# SwitchRouter1x6c.net
KiCad netlist of a schematic drawn in EAGLE
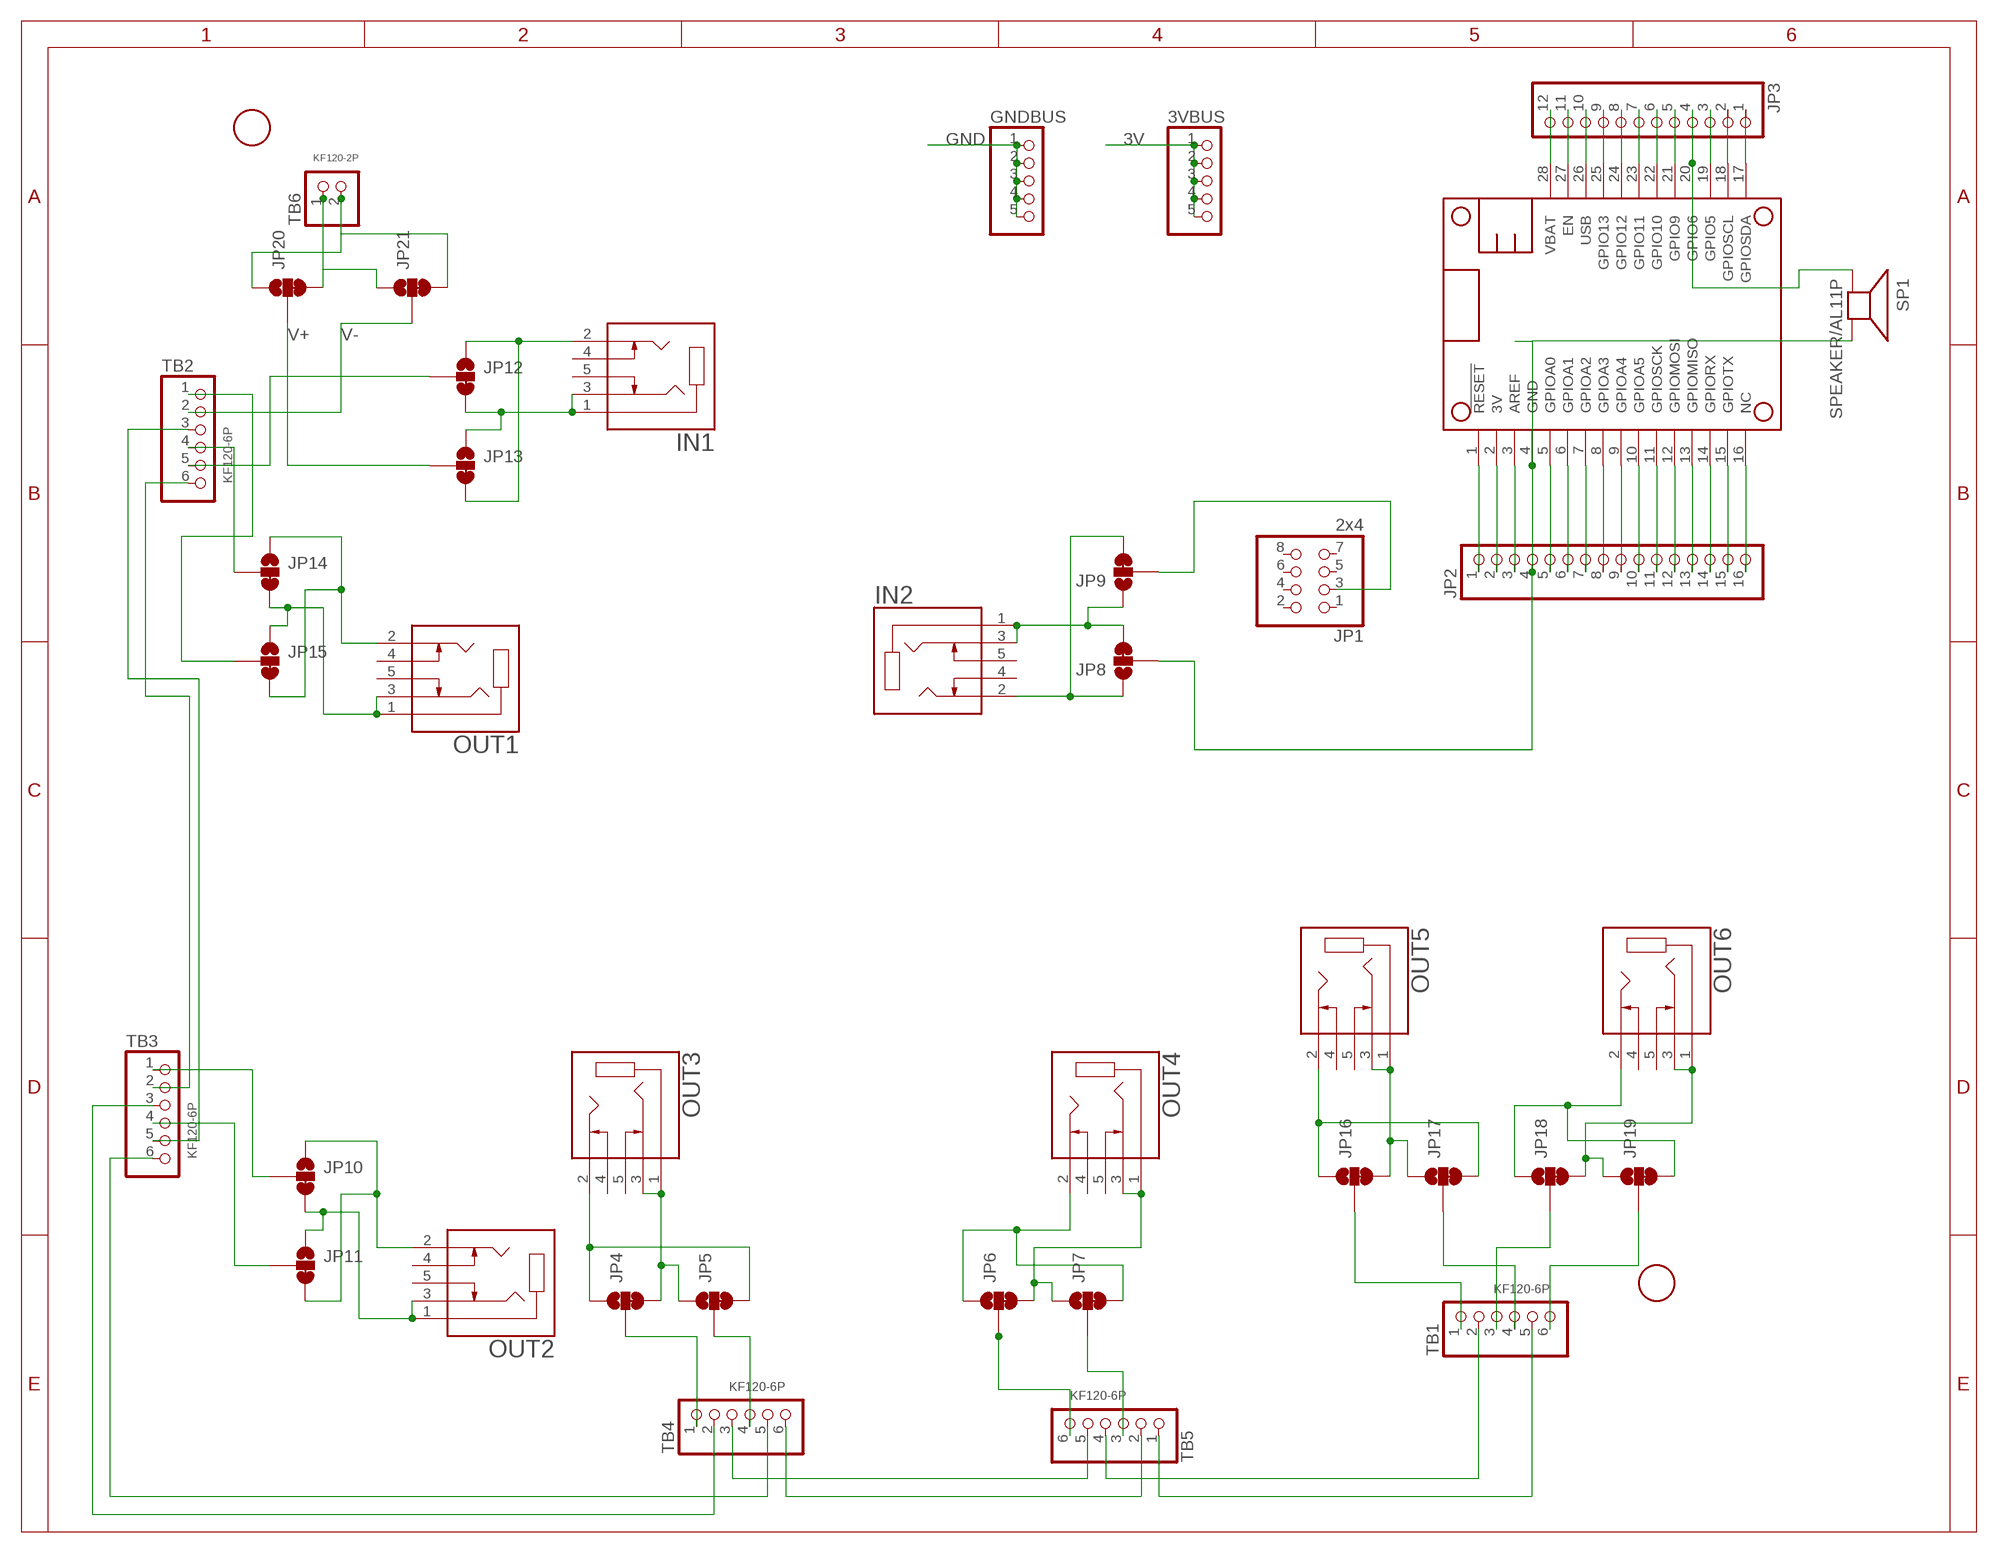
[diagram p0: schematic, sheet 1]

(export (version "E")
  (design (tool "Eeschema 10.0.6"))
  (components
    (comp (ref "3VBUS")
      (value "PINHD-1X55X2MM")
      (footprint "eagle-import:1_05X2MM")
      (libsource (lib "eagle-import") (part "PINHD-1X55X2MM"))
    )
    (comp (ref "GNDBUS")
      (value "PINHD-1X55X2MM")
      (footprint "eagle-import:1_05X2MM")
      (libsource (lib "eagle-import") (part "PINHD-1X55X2MM"))
    )
    (comp (ref "IN1")
      (value "SJ1-3535NG-PI")
      (footprint "eagle-import:CUI_SJ1-3535NG-PI")
      (fields (field (name "MANUFACTURER") "CUI"))
      (libsource (lib "eagle-import") (part "SJ1-3535NG-PI"))
    )
    (comp (ref "IN2")
      (value "SJ1-3535NG-PI")
      (footprint "eagle-import:CUI_SJ1-3535NG-PI")
      (fields (field (name "MANUFACTURER") "CUI"))
      (libsource (lib "eagle-import") (part "SJ1-3535NG-PI"))
    )
    (comp (ref "JP1")
      (value "2x4")
      (footprint "eagle-import:2X04")
      (libsource (lib "eagle-import") (part "PINHD-2X4"))
    )
    (comp (ref "JP2")
      (value "PINHD-1X16")
      (footprint "eagle-import:1X16")
      (libsource (lib "eagle-import") (part "PINHD-1X16"))
    )
    (comp (ref "JP3")
      (value "PINHD-1X12")
      (footprint "eagle-import:1X12")
      (libsource (lib "eagle-import") (part "PINHD-1X12"))
    )
    (comp (ref "JP4")
      (value "JUMPER-SMT_3_1-NC_TRACE_SILK")
      (footprint "eagle-import:SMT-JUMPER_3_1-NC_TRACE_SILK")
      (libsource (lib "eagle-import") (part "JUMPER-SMT_3_1-NC_TRACE_SILK"))
    )
    (comp (ref "JP5")
      (value "JUMPER-SMT_3_1-NC_TRACE_SILK")
      (footprint "eagle-import:SMT-JUMPER_3_1-NC_TRACE_SILK")
      (libsource (lib "eagle-import") (part "JUMPER-SMT_3_1-NC_TRACE_SILK"))
    )
    (comp (ref "JP6")
      (value "JUMPER-SMT_3_1-NC_TRACE_SILK")
      (footprint "eagle-import:SMT-JUMPER_3_1-NC_TRACE_SILK")
      (libsource (lib "eagle-import") (part "JUMPER-SMT_3_1-NC_TRACE_SILK"))
    )
    (comp (ref "JP7")
      (value "JUMPER-SMT_3_1-NC_TRACE_SILK")
      (footprint "eagle-import:SMT-JUMPER_3_1-NC_TRACE_SILK")
      (libsource (lib "eagle-import") (part "JUMPER-SMT_3_1-NC_TRACE_SILK"))
    )
    (comp (ref "JP8")
      (value "JUMPER-SMT_3_1-NC_TRACE_SILK")
      (footprint "eagle-import:SMT-JUMPER_3_1-NC_TRACE_SILK")
      (libsource (lib "eagle-import") (part "JUMPER-SMT_3_1-NC_TRACE_SILK"))
    )
    (comp (ref "JP9")
      (value "JUMPER-SMT_3_1-NC_TRACE_SILK")
      (footprint "eagle-import:SMT-JUMPER_3_1-NC_TRACE_SILK")
      (libsource (lib "eagle-import") (part "JUMPER-SMT_3_1-NC_TRACE_SILK"))
    )
    (comp (ref "JP10")
      (value "JUMPER-SMT_3_1-NC_TRACE_SILK")
      (footprint "eagle-import:SMT-JUMPER_3_1-NC_TRACE_SILK")
      (libsource (lib "eagle-import") (part "JUMPER-SMT_3_1-NC_TRACE_SILK"))
    )
    (comp (ref "JP11")
      (value "JUMPER-SMT_3_1-NC_TRACE_SILK")
      (footprint "eagle-import:SMT-JUMPER_3_1-NC_TRACE_SILK")
      (libsource (lib "eagle-import") (part "JUMPER-SMT_3_1-NC_TRACE_SILK"))
    )
    (comp (ref "JP12")
      (value "JUMPER-SMT_3_1-NC_TRACE_SILK")
      (footprint "eagle-import:SMT-JUMPER_3_1-NC_TRACE_SILK")
      (libsource (lib "eagle-import") (part "JUMPER-SMT_3_1-NC_TRACE_SILK"))
    )
    (comp (ref "JP13")
      (value "JUMPER-SMT_3_1-NC_TRACE_SILK")
      (footprint "eagle-import:SMT-JUMPER_3_1-NC_TRACE_SILK")
      (libsource (lib "eagle-import") (part "JUMPER-SMT_3_1-NC_TRACE_SILK"))
    )
    (comp (ref "JP14")
      (value "JUMPER-SMT_3_1-NC_TRACE_SILK")
      (footprint "eagle-import:SMT-JUMPER_3_1-NC_TRACE_SILK")
      (libsource (lib "eagle-import") (part "JUMPER-SMT_3_1-NC_TRACE_SILK"))
    )
    (comp (ref "JP15")
      (value "JUMPER-SMT_3_1-NC_TRACE_SILK")
      (footprint "eagle-import:SMT-JUMPER_3_1-NC_TRACE_SILK")
      (libsource (lib "eagle-import") (part "JUMPER-SMT_3_1-NC_TRACE_SILK"))
    )
    (comp (ref "JP16")
      (value "JUMPER-SMT_3_1-NC_TRACE_SILK")
      (footprint "eagle-import:SMT-JUMPER_3_1-NC_TRACE_SILK")
      (libsource (lib "eagle-import") (part "JUMPER-SMT_3_1-NC_TRACE_SILK"))
    )
    (comp (ref "JP17")
      (value "JUMPER-SMT_3_1-NC_TRACE_SILK")
      (footprint "eagle-import:SMT-JUMPER_3_1-NC_TRACE_SILK")
      (libsource (lib "eagle-import") (part "JUMPER-SMT_3_1-NC_TRACE_SILK"))
    )
    (comp (ref "JP18")
      (value "JUMPER-SMT_3_1-NC_TRACE_SILK")
      (footprint "eagle-import:SMT-JUMPER_3_1-NC_TRACE_SILK")
      (libsource (lib "eagle-import") (part "JUMPER-SMT_3_1-NC_TRACE_SILK"))
    )
    (comp (ref "JP19")
      (value "JUMPER-SMT_3_1-NC_TRACE_SILK")
      (footprint "eagle-import:SMT-JUMPER_3_1-NC_TRACE_SILK")
      (libsource (lib "eagle-import") (part "JUMPER-SMT_3_1-NC_TRACE_SILK"))
    )
    (comp (ref "JP20")
      (value "JUMPER-SMT_3_1-NC_TRACE_SILK")
      (footprint "eagle-import:SMT-JUMPER_3_1-NC_TRACE_SILK")
      (libsource (lib "eagle-import") (part "JUMPER-SMT_3_1-NC_TRACE_SILK"))
    )
    (comp (ref "JP21")
      (value "JUMPER-SMT_3_1-NC_TRACE_SILK")
      (footprint "eagle-import:SMT-JUMPER_3_1-NC_TRACE_SILK")
      (libsource (lib "eagle-import") (part "JUMPER-SMT_3_1-NC_TRACE_SILK"))
    )
    (comp (ref "MS1")
      (value "FEATHERWING_NODIM")
      (footprint "eagle-import:FEATHERWING_DIM")
      (libsource (lib "eagle-import") (part "FEATHERWING_NODIM"))
    )
    (comp (ref "OUT1")
      (value "SJ1-3535NG-PI")
      (footprint "eagle-import:CUI_SJ1-3535NG-PI")
      (fields (field (name "MANUFACTURER") "CUI"))
      (libsource (lib "eagle-import") (part "SJ1-3535NG-PI"))
    )
    (comp (ref "OUT2")
      (value "SJ1-3535NG-PI")
      (footprint "eagle-import:CUI_SJ1-3535NG-PI")
      (fields (field (name "MANUFACTURER") "CUI"))
      (libsource (lib "eagle-import") (part "SJ1-3535NG-PI"))
    )
    (comp (ref "OUT3")
      (value "SJ1-3535NG-PI")
      (footprint "eagle-import:CUI_SJ1-3535NG-PI")
      (fields (field (name "MANUFACTURER") "CUI"))
      (libsource (lib "eagle-import") (part "SJ1-3535NG-PI"))
    )
    (comp (ref "OUT4")
      (value "SJ1-3535NG-PI")
      (footprint "eagle-import:CUI_SJ1-3535NG-PI")
      (fields (field (name "MANUFACTURER") "CUI"))
      (libsource (lib "eagle-import") (part "SJ1-3535NG-PI"))
    )
    (comp (ref "OUT5")
      (value "SJ1-3535NG-PI")
      (footprint "eagle-import:CUI_SJ1-3535NG-PI")
      (fields (field (name "MANUFACTURER") "CUI"))
      (libsource (lib "eagle-import") (part "SJ1-3535NG-PI"))
    )
    (comp (ref "OUT6")
      (value "SJ1-3535NG-PI")
      (footprint "eagle-import:CUI_SJ1-3535NG-PI")
      (fields (field (name "MANUFACTURER") "CUI"))
      (libsource (lib "eagle-import") (part "SJ1-3535NG-PI"))
    )
    (comp (ref "SP1")
      (value "SPEAKER/AL11P")
      (footprint "eagle-import:AL11P")
      (libsource (lib "eagle-import") (part "SPEAKER/AL11P"))
    )
    (comp (ref "TB1")
      (value "KF120-6P")
      (footprint "eagle-import:KF120-6P_ROUND")
      (libsource (lib "eagle-import") (part "KF120-6P"))
    )
    (comp (ref "TB2")
      (value "KF120-6P")
      (footprint "eagle-import:KF120-6P_ROUND")
      (libsource (lib "eagle-import") (part "KF120-6P"))
    )
    (comp (ref "TB3")
      (value "KF120-6P")
      (footprint "eagle-import:KF120-6P_ROUND")
      (libsource (lib "eagle-import") (part "KF120-6P"))
    )
    (comp (ref "TB4")
      (value "KF120-6P")
      (footprint "eagle-import:KF120-6P_ROUND")
      (libsource (lib "eagle-import") (part "KF120-6P"))
    )
    (comp (ref "TB5")
      (value "KF120-6P")
      (footprint "eagle-import:KF120-6P_ROUND")
      (libsource (lib "eagle-import") (part "KF120-6P"))
    )
    (comp (ref "TB6")
      (value "KF120-2P")
      (footprint "eagle-import:KF120-2P_ROUND")
      (libsource (lib "eagle-import") (part "KF120-2P"))
    )
    (comp (ref "U$2")
      (value "FIDUCIAL")
      (footprint "eagle-import:FIDUCIAL_1MM")
      (libsource (lib "eagle-import") (part "FIDUCIAL"))
    )
    (comp (ref "U$3")
      (value "FIDUCIAL")
      (footprint "eagle-import:FIDUCIAL_1MM")
      (libsource (lib "eagle-import") (part "FIDUCIAL"))
    )
  )
  (nets
    (net (code "1") (name "/3V") (class "Default")
      (node (ref "3VBUS") (pin "1") (pinfunction "1_1") (pintype "passive"))
      (node (ref "3VBUS") (pin "2") (pinfunction "2_2") (pintype "passive"))
      (node (ref "3VBUS") (pin "3") (pinfunction "3_3") (pintype "passive"))
      (node (ref "3VBUS") (pin "4") (pinfunction "4_4") (pintype "passive"))
      (node (ref "3VBUS") (pin "5") (pinfunction "5_5") (pintype "passive"))
      (node (ref "JP2") (pin "2") (pinfunction "2_2") (pintype "passive"))
      (node (ref "MS1") (pin "2") (pinfunction "3V_2") (pintype "power_in"))
    )
    (net (code "2") (name "/GND") (class "Default")
      (node (ref "GNDBUS") (pin "1") (pinfunction "1_1") (pintype "passive"))
      (node (ref "GNDBUS") (pin "2") (pinfunction "2_2") (pintype "passive"))
      (node (ref "GNDBUS") (pin "3") (pinfunction "3_3") (pintype "passive"))
      (node (ref "GNDBUS") (pin "4") (pinfunction "4_4") (pintype "passive"))
      (node (ref "GNDBUS") (pin "5") (pinfunction "5_5") (pintype "passive"))
      (node (ref "JP2") (pin "4") (pinfunction "4_4") (pintype "passive"))
      (node (ref "JP8") (pin "2") (pinfunction "2_2") (pintype "passive"))
      (node (ref "MS1") (pin "4") (pinfunction "GND_4") (pintype "power_in"))
      (node (ref "SP1") (pin "-") (pinfunction "-_-") (pintype "passive"))
    )
    (net (code "3") (name "/V+") (class "Default")
      (node (ref "JP13") (pin "2") (pinfunction "2_2") (pintype "passive"))
      (node (ref "JP20") (pin "2") (pinfunction "2_2") (pintype "passive"))
    )
    (net (code "4") (name "/V-") (class "Default")
      (node (ref "JP21") (pin "2") (pinfunction "2_2") (pintype "passive"))
      (node (ref "TB2") (pin "2") (pinfunction "2_2") (pintype "passive"))
    )
    (net (code "5") (name "Net-(IN1-Pad1)") (class "Default")
      (node (ref "IN1") (pin "1") (pinfunction "1_1") (pintype "passive"))
      (node (ref "IN1") (pin "3") (pinfunction "3_3") (pintype "passive"))
      (node (ref "JP12") (pin "3") (pinfunction "3_3") (pintype "passive"))
      (node (ref "JP13") (pin "1") (pinfunction "1_1") (pintype "passive"))
    )
    (net (code "6") (name "Net-(IN1-Pad2)") (class "Default")
      (node (ref "IN1") (pin "2") (pinfunction "2_2") (pintype "passive"))
      (node (ref "JP12") (pin "1") (pinfunction "1_1") (pintype "passive"))
      (node (ref "JP13") (pin "3") (pinfunction "3_3") (pintype "passive"))
    )
    (net (code "7") (name "Net-(IN2-Pad1)") (class "Default")
      (node (ref "IN2") (pin "1") (pinfunction "1_1") (pintype "passive"))
      (node (ref "IN2") (pin "3") (pinfunction "3_3") (pintype "passive"))
      (node (ref "JP8") (pin "3") (pinfunction "3_3") (pintype "passive"))
      (node (ref "JP9") (pin "1") (pinfunction "1_1") (pintype "passive"))
    )
    (net (code "8") (name "Net-(IN2-Pad2)") (class "Default")
      (node (ref "IN2") (pin "2") (pinfunction "2_2") (pintype "passive"))
      (node (ref "JP8") (pin "1") (pinfunction "1_1") (pintype "passive"))
      (node (ref "JP9") (pin "3") (pinfunction "3_3") (pintype "passive"))
    )
    (net (code "9") (name "Net-(JP1-Pad3)") (class "Default")
      (node (ref "JP1") (pin "3") (pinfunction "3_3") (pintype "passive"))
      (node (ref "JP9") (pin "2") (pinfunction "2_2") (pintype "passive"))
    )
    (net (code "10") (name "Net-(JP4-Pad1)") (class "Default")
      (node (ref "JP4") (pin "1") (pinfunction "1_1") (pintype "passive"))
      (node (ref "JP5") (pin "3") (pinfunction "3_3") (pintype "passive"))
      (node (ref "OUT3") (pin "2") (pinfunction "2_2") (pintype "passive"))
    )
    (net (code "11") (name "Net-(JP4-Pad2)") (class "Default")
      (node (ref "JP4") (pin "2") (pinfunction "2_2") (pintype "passive"))
      (node (ref "TB4") (pin "1") (pinfunction "1_1") (pintype "passive"))
    )
    (net (code "12") (name "Net-(JP4-Pad3)") (class "Default")
      (node (ref "JP4") (pin "3") (pinfunction "3_3") (pintype "passive"))
      (node (ref "JP5") (pin "1") (pinfunction "1_1") (pintype "passive"))
      (node (ref "OUT3") (pin "1") (pinfunction "1_1") (pintype "passive"))
      (node (ref "OUT3") (pin "3") (pinfunction "3_3") (pintype "passive"))
    )
    (net (code "13") (name "Net-(JP5-Pad2)") (class "Default")
      (node (ref "JP5") (pin "2") (pinfunction "2_2") (pintype "passive"))
      (node (ref "TB4") (pin "4") (pinfunction "4_4") (pintype "passive"))
    )
    (net (code "14") (name "Net-(JP6-Pad1)") (class "Default")
      (node (ref "JP6") (pin "1") (pinfunction "1_1") (pintype "passive"))
      (node (ref "JP7") (pin "3") (pinfunction "3_3") (pintype "passive"))
      (node (ref "OUT4") (pin "2") (pinfunction "2_2") (pintype "passive"))
    )
    (net (code "15") (name "Net-(JP6-Pad2)") (class "Default")
      (node (ref "JP6") (pin "2") (pinfunction "2_2") (pintype "passive"))
      (node (ref "TB5") (pin "6") (pinfunction "6_6") (pintype "passive"))
    )
    (net (code "16") (name "Net-(JP6-Pad3)") (class "Default")
      (node (ref "JP6") (pin "3") (pinfunction "3_3") (pintype "passive"))
      (node (ref "JP7") (pin "1") (pinfunction "1_1") (pintype "passive"))
      (node (ref "OUT4") (pin "1") (pinfunction "1_1") (pintype "passive"))
      (node (ref "OUT4") (pin "3") (pinfunction "3_3") (pintype "passive"))
    )
    (net (code "17") (name "Net-(JP7-Pad2)") (class "Default")
      (node (ref "JP7") (pin "2") (pinfunction "2_2") (pintype "passive"))
      (node (ref "TB5") (pin "3") (pinfunction "3_3") (pintype "passive"))
    )
    (net (code "18") (name "Net-(JP10-Pad1)") (class "Default")
      (node (ref "JP10") (pin "1") (pinfunction "1_1") (pintype "passive"))
      (node (ref "JP11") (pin "3") (pinfunction "3_3") (pintype "passive"))
      (node (ref "OUT2") (pin "2") (pinfunction "2_2") (pintype "passive"))
    )
    (net (code "19") (name "Net-(JP10-Pad2)") (class "Default")
      (node (ref "JP10") (pin "2") (pinfunction "2_2") (pintype "passive"))
      (node (ref "TB3") (pin "1") (pinfunction "1_1") (pintype "passive"))
    )
    (net (code "20") (name "Net-(JP10-Pad3)") (class "Default")
      (node (ref "JP10") (pin "3") (pinfunction "3_3") (pintype "passive"))
      (node (ref "JP11") (pin "1") (pinfunction "1_1") (pintype "passive"))
      (node (ref "OUT2") (pin "1") (pinfunction "1_1") (pintype "passive"))
      (node (ref "OUT2") (pin "3") (pinfunction "3_3") (pintype "passive"))
    )
    (net (code "21") (name "Net-(JP11-Pad2)") (class "Default")
      (node (ref "JP11") (pin "2") (pinfunction "2_2") (pintype "passive"))
      (node (ref "TB3") (pin "4") (pinfunction "4_4") (pintype "passive"))
    )
    (net (code "22") (name "Net-(JP12-Pad2)") (class "Default")
      (node (ref "JP12") (pin "2") (pinfunction "2_2") (pintype "passive"))
      (node (ref "TB2") (pin "5") (pinfunction "5_5") (pintype "passive"))
    )
    (net (code "23") (name "Net-(JP14-Pad1)") (class "Default")
      (node (ref "JP14") (pin "1") (pinfunction "1_1") (pintype "passive"))
      (node (ref "JP15") (pin "3") (pinfunction "3_3") (pintype "passive"))
      (node (ref "OUT1") (pin "2") (pinfunction "2_2") (pintype "passive"))
    )
    (net (code "24") (name "Net-(JP14-Pad2)") (class "Default")
      (node (ref "JP14") (pin "2") (pinfunction "2_2") (pintype "passive"))
      (node (ref "TB2") (pin "4") (pinfunction "4_4") (pintype "passive"))
    )
    (net (code "25") (name "Net-(JP14-Pad3)") (class "Default")
      (node (ref "JP14") (pin "3") (pinfunction "3_3") (pintype "passive"))
      (node (ref "JP15") (pin "1") (pinfunction "1_1") (pintype "passive"))
      (node (ref "OUT1") (pin "1") (pinfunction "1_1") (pintype "passive"))
      (node (ref "OUT1") (pin "3") (pinfunction "3_3") (pintype "passive"))
    )
    (net (code "26") (name "Net-(JP15-Pad2)") (class "Default")
      (node (ref "JP15") (pin "2") (pinfunction "2_2") (pintype "passive"))
      (node (ref "TB2") (pin "1") (pinfunction "1_1") (pintype "passive"))
    )
    (net (code "27") (name "Net-(JP16-Pad1)") (class "Default")
      (node (ref "JP16") (pin "1") (pinfunction "1_1") (pintype "passive"))
      (node (ref "JP17") (pin "3") (pinfunction "3_3") (pintype "passive"))
      (node (ref "OUT5") (pin "2") (pinfunction "2_2") (pintype "passive"))
    )
    (net (code "28") (name "Net-(JP16-Pad2)") (class "Default")
      (node (ref "JP16") (pin "2") (pinfunction "2_2") (pintype "passive"))
      (node (ref "TB1") (pin "1") (pinfunction "1_1") (pintype "passive"))
    )
    (net (code "29") (name "Net-(JP16-Pad3)") (class "Default")
      (node (ref "JP16") (pin "3") (pinfunction "3_3") (pintype "passive"))
      (node (ref "JP17") (pin "1") (pinfunction "1_1") (pintype "passive"))
      (node (ref "OUT5") (pin "1") (pinfunction "1_1") (pintype "passive"))
      (node (ref "OUT5") (pin "3") (pinfunction "3_3") (pintype "passive"))
    )
    (net (code "30") (name "Net-(JP17-Pad2)") (class "Default")
      (node (ref "JP17") (pin "2") (pinfunction "2_2") (pintype "passive"))
      (node (ref "TB1") (pin "4") (pinfunction "4_4") (pintype "passive"))
    )
    (net (code "31") (name "Net-(JP18-Pad1)") (class "Default")
      (node (ref "JP18") (pin "1") (pinfunction "1_1") (pintype "passive"))
      (node (ref "JP19") (pin "3") (pinfunction "3_3") (pintype "passive"))
      (node (ref "OUT6") (pin "2") (pinfunction "2_2") (pintype "passive"))
    )
    (net (code "32") (name "Net-(JP18-Pad2)") (class "Default")
      (node (ref "JP18") (pin "2") (pinfunction "2_2") (pintype "passive"))
      (node (ref "TB1") (pin "3") (pinfunction "3_3") (pintype "passive"))
    )
    (net (code "33") (name "Net-(JP18-Pad3)") (class "Default")
      (node (ref "JP18") (pin "3") (pinfunction "3_3") (pintype "passive"))
      (node (ref "JP19") (pin "1") (pinfunction "1_1") (pintype "passive"))
      (node (ref "OUT6") (pin "1") (pinfunction "1_1") (pintype "passive"))
      (node (ref "OUT6") (pin "3") (pinfunction "3_3") (pintype "passive"))
    )
    (net (code "34") (name "Net-(JP19-Pad2)") (class "Default")
      (node (ref "JP19") (pin "2") (pinfunction "2_2") (pintype "passive"))
      (node (ref "TB1") (pin "6") (pinfunction "6_6") (pintype "passive"))
    )
    (net (code "35") (name "Net-(JP20-Pad1)") (class "Default")
      (node (ref "JP20") (pin "1") (pinfunction "1_1") (pintype "passive"))
      (node (ref "JP21") (pin "3") (pinfunction "3_3") (pintype "passive"))
      (node (ref "TB6") (pin "2") (pinfunction "2_2") (pintype "passive"))
    )
    (net (code "36") (name "Net-(JP20-Pad3)") (class "Default")
      (node (ref "JP20") (pin "3") (pinfunction "3_3") (pintype "passive"))
      (node (ref "JP21") (pin "1") (pinfunction "1_1") (pintype "passive"))
      (node (ref "TB6") (pin "1") (pinfunction "1_1") (pintype "passive"))
    )
    (net (code "37") (name "Net-(MS1-AREF)") (class "Default")
      (node (ref "JP2") (pin "3") (pinfunction "3_3") (pintype "passive"))
      (node (ref "MS1") (pin "3") (pinfunction "AREF_3") (pintype "passive"))
    )
    (net (code "38") (name "Net-(MS1-EN)") (class "Default")
      (node (ref "JP3") (pin "11") (pinfunction "11_11") (pintype "passive"))
      (node (ref "MS1") (pin "27") (pinfunction "EN_27") (pintype "passive"))
    )
    (net (code "39") (name "Net-(MS1-GPIO5)") (class "Default")
      (node (ref "JP3") (pin "3") (pinfunction "3_3") (pintype "passive"))
      (node (ref "MS1") (pin "19") (pinfunction "GPIO5_19") (pintype "bidirectional"))
    )
    (net (code "40") (name "Net-(MS1-GPIO6)") (class "Default")
      (node (ref "JP3") (pin "4") (pinfunction "4_4") (pintype "passive"))
      (node (ref "MS1") (pin "20") (pinfunction "GPIO6_20") (pintype "bidirectional"))
      (node (ref "SP1") (pin "+") (pinfunction "+_+") (pintype "passive"))
    )
    (net (code "41") (name "Net-(MS1-GPIO9)") (class "Default")
      (node (ref "JP3") (pin "5") (pinfunction "5_5") (pintype "passive"))
      (node (ref "MS1") (pin "21") (pinfunction "GPIO9_21") (pintype "bidirectional"))
    )
    (net (code "42") (name "Net-(MS1-GPIO10)") (class "Default")
      (node (ref "JP3") (pin "6") (pinfunction "6_6") (pintype "passive"))
      (node (ref "MS1") (pin "22") (pinfunction "GPIO10_22") (pintype "bidirectional"))
    )
    (net (code "43") (name "Net-(MS1-GPIO11)") (class "Default")
      (node (ref "JP3") (pin "7") (pinfunction "7_7") (pintype "passive"))
      (node (ref "MS1") (pin "23") (pinfunction "GPIO11_23") (pintype "bidirectional"))
    )
    (net (code "44") (name "Net-(MS1-GPIO12)") (class "Default")
      (node (ref "JP3") (pin "8") (pinfunction "8_8") (pintype "passive"))
      (node (ref "MS1") (pin "24") (pinfunction "GPIO12_24") (pintype "bidirectional"))
    )
    (net (code "45") (name "Net-(MS1-GPIO13)") (class "Default")
      (node (ref "JP3") (pin "9") (pinfunction "9_9") (pintype "passive"))
      (node (ref "MS1") (pin "25") (pinfunction "GPIO13_25") (pintype "bidirectional"))
    )
    (net (code "46") (name "Net-(MS1-GPIOA0)") (class "Default")
      (node (ref "JP2") (pin "5") (pinfunction "5_5") (pintype "passive"))
      (node (ref "MS1") (pin "5") (pinfunction "GPIOA0_5") (pintype "bidirectional"))
    )
    (net (code "47") (name "Net-(MS1-GPIOA1)") (class "Default")
      (node (ref "JP2") (pin "6") (pinfunction "6_6") (pintype "passive"))
      (node (ref "MS1") (pin "6") (pinfunction "GPIOA1_6") (pintype "bidirectional"))
    )
    (net (code "48") (name "Net-(MS1-GPIOA2)") (class "Default")
      (node (ref "JP2") (pin "7") (pinfunction "7_7") (pintype "passive"))
      (node (ref "MS1") (pin "7") (pinfunction "GPIOA2_7") (pintype "bidirectional"))
    )
    (net (code "49") (name "Net-(MS1-GPIOA3)") (class "Default")
      (node (ref "JP2") (pin "8") (pinfunction "8_8") (pintype "passive"))
      (node (ref "MS1") (pin "8") (pinfunction "GPIOA3_8") (pintype "bidirectional"))
    )
    (net (code "50") (name "Net-(MS1-GPIOA4)") (class "Default")
      (node (ref "JP2") (pin "9") (pinfunction "9_9") (pintype "passive"))
      (node (ref "MS1") (pin "9") (pinfunction "GPIOA4_9") (pintype "bidirectional"))
    )
    (net (code "51") (name "Net-(MS1-GPIOA5)") (class "Default")
      (node (ref "JP2") (pin "10") (pinfunction "10_10") (pintype "passive"))
      (node (ref "MS1") (pin "10") (pinfunction "GPIOA5_10") (pintype "bidirectional"))
    )
    (net (code "52") (name "Net-(MS1-GPIOMISO)") (class "Default")
      (node (ref "JP2") (pin "13") (pinfunction "13_13") (pintype "passive"))
      (node (ref "MS1") (pin "13") (pinfunction "GPIOMISO_13") (pintype "bidirectional"))
    )
    (net (code "53") (name "Net-(MS1-GPIOMOSI)") (class "Default")
      (node (ref "JP2") (pin "12") (pinfunction "12_12") (pintype "passive"))
      (node (ref "MS1") (pin "12") (pinfunction "GPIOMOSI_12") (pintype "bidirectional"))
    )
    (net (code "54") (name "Net-(MS1-GPIORX)") (class "Default")
      (node (ref "JP2") (pin "14") (pinfunction "14_14") (pintype "passive"))
      (node (ref "MS1") (pin "14") (pinfunction "GPIORX_14") (pintype "bidirectional"))
    )
    (net (code "55") (name "Net-(MS1-GPIOSCK)") (class "Default")
      (node (ref "JP2") (pin "11") (pinfunction "11_11") (pintype "passive"))
      (node (ref "MS1") (pin "11") (pinfunction "GPIOSCK_11") (pintype "bidirectional"))
    )
    (net (code "56") (name "Net-(MS1-GPIOSCL)") (class "Default")
      (node (ref "JP3") (pin "2") (pinfunction "2_2") (pintype "passive"))
      (node (ref "MS1") (pin "18") (pinfunction "GPIOSCL_18") (pintype "bidirectional"))
    )
    (net (code "57") (name "Net-(MS1-GPIOSDA)") (class "Default")
      (node (ref "JP3") (pin "1") (pinfunction "1_1") (pintype "passive"))
      (node (ref "MS1") (pin "17") (pinfunction "GPIOSDA_17") (pintype "bidirectional"))
    )
    (net (code "58") (name "Net-(MS1-GPIOTX)") (class "Default")
      (node (ref "JP2") (pin "15") (pinfunction "15_15") (pintype "passive"))
      (node (ref "MS1") (pin "15") (pinfunction "GPIOTX_15") (pintype "bidirectional"))
    )
    (net (code "59") (name "Net-(MS1-NC)") (class "Default")
      (node (ref "JP2") (pin "16") (pinfunction "16_16") (pintype "passive"))
      (node (ref "MS1") (pin "16") (pinfunction "NC_16") (pintype "passive"))
    )
    (net (code "60") (name "Net-(MS1-USB)") (class "Default")
      (node (ref "JP3") (pin "10") (pinfunction "10_10") (pintype "passive"))
      (node (ref "MS1") (pin "26") (pinfunction "USB_26") (pintype "power_in"))
    )
    (net (code "61") (name "Net-(MS1-VBAT)") (class "Default")
      (node (ref "JP3") (pin "12") (pinfunction "12_12") (pintype "passive"))
      (node (ref "MS1") (pin "28") (pinfunction "VBAT_28") (pintype "power_in"))
    )
    (net (code "62") (name "Net-(MS1-~{RESET})") (class "Default")
      (node (ref "JP2") (pin "1") (pinfunction "1_1") (pintype "passive"))
      (node (ref "MS1") (pin "1") (pinfunction "~{RESET}_1") (pintype "input"))
    )
    (net (code "63") (name "Net-(TB1-Pad2)") (class "Default")
      (node (ref "TB1") (pin "2") (pinfunction "2_2") (pintype "passive"))
      (node (ref "TB5") (pin "4") (pinfunction "4_4") (pintype "passive"))
    )
    (net (code "64") (name "Net-(TB1-Pad5)") (class "Default")
      (node (ref "TB1") (pin "5") (pinfunction "5_5") (pintype "passive"))
      (node (ref "TB5") (pin "1") (pinfunction "1_1") (pintype "passive"))
    )
    (net (code "65") (name "Net-(TB2-Pad3)") (class "Default")
      (node (ref "TB2") (pin "3") (pinfunction "3_3") (pintype "passive"))
      (node (ref "TB3") (pin "5") (pinfunction "5_5") (pintype "passive"))
    )
    (net (code "66") (name "Net-(TB2-Pad6)") (class "Default")
      (node (ref "TB2") (pin "6") (pinfunction "6_6") (pintype "passive"))
      (node (ref "TB3") (pin "2") (pinfunction "2_2") (pintype "passive"))
    )
    (net (code "67") (name "Net-(TB3-Pad3)") (class "Default")
      (node (ref "TB3") (pin "3") (pinfunction "3_3") (pintype "passive"))
      (node (ref "TB4") (pin "2") (pinfunction "2_2") (pintype "passive"))
    )
    (net (code "68") (name "Net-(TB3-Pad6)") (class "Default")
      (node (ref "TB3") (pin "6") (pinfunction "6_6") (pintype "passive"))
      (node (ref "TB4") (pin "5") (pinfunction "5_5") (pintype "passive"))
    )
    (net (code "69") (name "Net-(TB4-Pad3)") (class "Default")
      (node (ref "TB4") (pin "3") (pinfunction "3_3") (pintype "passive"))
      (node (ref "TB5") (pin "5") (pinfunction "5_5") (pintype "passive"))
    )
    (net (code "70") (name "Net-(TB4-Pad6)") (class "Default")
      (node (ref "TB4") (pin "6") (pinfunction "6_6") (pintype "passive"))
      (node (ref "TB5") (pin "2") (pinfunction "2_2") (pintype "passive"))
    )
    (net (code "71") (name "unconnected-(IN1-Pad4)") (class "Default")
      (node (ref "IN1") (pin "4") (pinfunction "4_4") (pintype "passive"))
    )
    (net (code "72") (name "unconnected-(IN1-Pad5)") (class "Default")
      (node (ref "IN1") (pin "5") (pinfunction "5_5") (pintype "passive"))
    )
    (net (code "73") (name "unconnected-(IN2-Pad4)") (class "Default")
      (node (ref "IN2") (pin "4") (pinfunction "4_4") (pintype "passive"))
    )
    (net (code "74") (name "unconnected-(IN2-Pad5)") (class "Default")
      (node (ref "IN2") (pin "5") (pinfunction "5_5") (pintype "passive"))
    )
    (net (code "75") (name "unconnected-(JP1-Pad1)") (class "Default")
      (node (ref "JP1") (pin "1") (pinfunction "1_1") (pintype "passive"))
    )
    (net (code "76") (name "unconnected-(JP1-Pad2)") (class "Default")
      (node (ref "JP1") (pin "2") (pinfunction "2_2") (pintype "passive"))
    )
    (net (code "77") (name "unconnected-(JP1-Pad4)") (class "Default")
      (node (ref "JP1") (pin "4") (pinfunction "4_4") (pintype "passive"))
    )
    (net (code "78") (name "unconnected-(JP1-Pad5)") (class "Default")
      (node (ref "JP1") (pin "5") (pinfunction "5_5") (pintype "passive"))
    )
    (net (code "79") (name "unconnected-(JP1-Pad6)") (class "Default")
      (node (ref "JP1") (pin "6") (pinfunction "6_6") (pintype "passive"))
    )
    (net (code "80") (name "unconnected-(JP1-Pad7)") (class "Default")
      (node (ref "JP1") (pin "7") (pinfunction "7_7") (pintype "passive"))
    )
    (net (code "81") (name "unconnected-(JP1-Pad8)") (class "Default")
      (node (ref "JP1") (pin "8") (pinfunction "8_8") (pintype "passive"))
    )
    (net (code "82") (name "unconnected-(OUT1-Pad4)") (class "Default")
      (node (ref "OUT1") (pin "4") (pinfunction "4_4") (pintype "passive"))
    )
    (net (code "83") (name "unconnected-(OUT1-Pad5)") (class "Default")
      (node (ref "OUT1") (pin "5") (pinfunction "5_5") (pintype "passive"))
    )
    (net (code "84") (name "unconnected-(OUT2-Pad4)") (class "Default")
      (node (ref "OUT2") (pin "4") (pinfunction "4_4") (pintype "passive"))
    )
    (net (code "85") (name "unconnected-(OUT2-Pad5)") (class "Default")
      (node (ref "OUT2") (pin "5") (pinfunction "5_5") (pintype "passive"))
    )
    (net (code "86") (name "unconnected-(OUT3-Pad4)") (class "Default")
      (node (ref "OUT3") (pin "4") (pinfunction "4_4") (pintype "passive"))
    )
    (net (code "87") (name "unconnected-(OUT3-Pad5)") (class "Default")
      (node (ref "OUT3") (pin "5") (pinfunction "5_5") (pintype "passive"))
    )
    (net (code "88") (name "unconnected-(OUT4-Pad4)") (class "Default")
      (node (ref "OUT4") (pin "4") (pinfunction "4_4") (pintype "passive"))
    )
    (net (code "89") (name "unconnected-(OUT4-Pad5)") (class "Default")
      (node (ref "OUT4") (pin "5") (pinfunction "5_5") (pintype "passive"))
    )
    (net (code "90") (name "unconnected-(OUT5-Pad4)") (class "Default")
      (node (ref "OUT5") (pin "4") (pinfunction "4_4") (pintype "passive"))
    )
    (net (code "91") (name "unconnected-(OUT5-Pad5)") (class "Default")
      (node (ref "OUT5") (pin "5") (pinfunction "5_5") (pintype "passive"))
    )
    (net (code "92") (name "unconnected-(OUT6-Pad4)") (class "Default")
      (node (ref "OUT6") (pin "4") (pinfunction "4_4") (pintype "passive"))
    )
    (net (code "93") (name "unconnected-(OUT6-Pad5)") (class "Default")
      (node (ref "OUT6") (pin "5") (pinfunction "5_5") (pintype "passive"))
    )
  )
)
